# Sheet2.net
KiCad netlist of a schematic drawn in Altium Designer
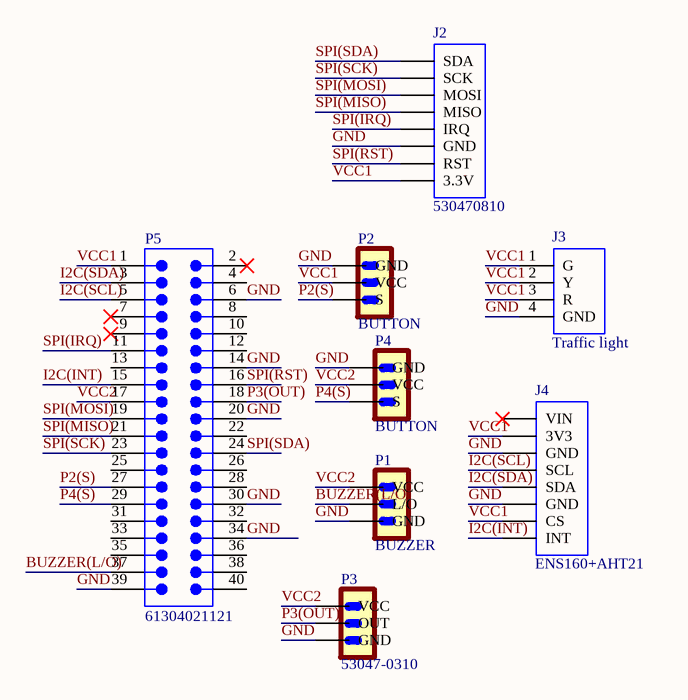
[diagram p0: Sheet2.SchDoc]

(export (version "E")
  (design (tool "Eeschema 10.0.6"))
  (components
    (comp (ref "J2") (value "530470810") (footprint "SPI") (libsource (lib "Schlib1") (part "530470810")))
    (comp (ref "J3")
      (value "Traffic light")
      (footprint "Traffic light")
      (description "2.50mm Pitch SPOXâ„¢ Wire-to-Board Header, Vertical, Shrouded, 4 Circuits, Tin (Sn) Plating")
      (fields (field (name "MF") "Molex") (field (name "MP") "22035045"))
      (libsource (lib "Schlib1") (part "Traffic light"))
    )
    (comp (ref "J4")
      (value "ENS160+AHT21")
      (footprint "ENS160+AHT21")
      (fields (field (name "MP") "530470810"))
      (libsource (lib "Schlib1") (part "ENS160+AHT21"))
    )
    (comp (ref "P1")
      (value "BUZZER")
      (footprint "BUZZER")
      (description "Connector Header Through Hole 3 position 0.049 (1.25mm)")
      (fields (field (name "MF") "Molex") (field (name "MP") "53047-0310"))
      (libsource (lib "Schlib1") (part "BUZZER"))
    )
    (comp (ref "P2")
      (value "BUTTON")
      (footprint "Button")
      (description "Connector Header Through Hole 3 position 0.049 (1.25mm)")
      (fields (field (name "MF") "Molex") (field (name "MP") "53047-0310"))
      (libsource (lib "") (part "BUTTON_1"))
    )
    (comp (ref "P3")
      (value "53047-0310")
      (footprint "SR505")
      (description "Connector Header Through Hole 3 position 0.049 (1.25mm)")
      (fields (field (name "MF") "Molex"))
      (libsource (lib "Schlib1") (part "53047-0310"))
    )
    (comp (ref "P4")
      (value "BUTTON")
      (footprint "Button2")
      (description "Connector Header Through Hole 3 position 0.049 (1.25mm)")
      (fields (field (name "MF") "Molex") (field (name "MP") "53047-0310"))
      (libsource (lib "Schlib1") (part "BUTTON"))
    )
    (comp (ref "P5")
      (value "61304021121")
      (footprint "61304021121")
      (description "WR-PHD Straight Male, PCB Header, Through Hole, 2 Rows, 40 Contacts, 2.54mm Pitch")
      (libsource (lib "Schlib1") (part "CMP-1502-01135-4"))
    )
  )
  (nets
    (net (code "1") (name "/BUZZER(L{slash}O)") (class "Default")
      (node (ref "P1") (pin "2") (pinfunction "L/O_2") (pintype "passive"))
      (node (ref "P5") (pin "37") (pinfunction "37_37") (pintype "passive"))
    )
    (net (code "2") (name "/GND") (class "Default")
      (node (ref "J2") (pin "6") (pinfunction "GND_6") (pintype "passive"))
      (node (ref "J3") (pin "4") (pinfunction "GND_4") (pintype "passive"))
      (node (ref "J4") (pin "3") (pinfunction "GND_3") (pintype "passive"))
      (node (ref "P1") (pin "1") (pinfunction "GND_1") (pintype "passive"))
      (node (ref "P2") (pin "41") (pinfunction "GND_41") (pintype "passive"))
      (node (ref "P3") (pin "1") (pinfunction "GND_1") (pintype "passive"))
      (node (ref "P4") (pin "44") (pinfunction "GND_44") (pintype "passive"))
      (node (ref "P5") (pin "14") (pinfunction "14_14") (pintype "passive"))
      (node (ref "P5") (pin "20") (pinfunction "20_20") (pintype "passive"))
      (node (ref "P5") (pin "30") (pinfunction "30_30") (pintype "passive"))
      (node (ref "P5") (pin "34") (pinfunction "34_34") (pintype "passive"))
      (node (ref "P5") (pin "39") (pinfunction "39_39") (pintype "passive"))
      (node (ref "P5") (pin "6") (pinfunction "6_6") (pintype "passive"))
    )
    (net (code "3") (name "/I2C(INT)") (class "Default")
      (node (ref "J4") (pin "8") (pinfunction "INT_8") (pintype "passive"))
      (node (ref "P5") (pin "15") (pinfunction "15_15") (pintype "passive"))
    )
    (net (code "4") (name "/I2C(SCL)") (class "Default")
      (node (ref "J4") (pin "4") (pinfunction "SCL_4") (pintype "passive"))
      (node (ref "P5") (pin "5") (pinfunction "5_5") (pintype "passive"))
    )
    (net (code "5") (name "/I2C(SDA)") (class "Default")
      (node (ref "J4") (pin "5") (pinfunction "SDA_5") (pintype "passive"))
      (node (ref "P5") (pin "3") (pinfunction "3_3") (pintype "passive"))
    )
    (net (code "6") (name "/P2(S)") (class "Default")
      (node (ref "P2") (pin "42") (pinfunction "S_42") (pintype "passive"))
      (node (ref "P5") (pin "27") (pinfunction "27_27") (pintype "passive"))
    )
    (net (code "7") (name "/P3(OUT)") (class "Default")
      (node (ref "P3") (pin "2") (pinfunction "OUT_2") (pintype "passive"))
      (node (ref "P5") (pin "18") (pinfunction "18_18") (pintype "passive"))
    )
    (net (code "8") (name "/P4(S)") (class "Default")
      (node (ref "P4") (pin "45") (pinfunction "S_45") (pintype "passive"))
      (node (ref "P5") (pin "29") (pinfunction "29_29") (pintype "passive"))
    )
    (net (code "9") (name "/SPI(IRQ)") (class "Default")
      (node (ref "J2") (pin "5") (pinfunction "IRQ_5") (pintype "passive"))
      (node (ref "P5") (pin "11") (pinfunction "11_11") (pintype "passive"))
    )
    (net (code "10") (name "/SPI(MISO)") (class "Default")
      (node (ref "J2") (pin "4") (pinfunction "MISO_4") (pintype "passive"))
      (node (ref "P5") (pin "21") (pinfunction "21_21") (pintype "passive"))
    )
    (net (code "11") (name "/SPI(MOSI)") (class "Default")
      (node (ref "J2") (pin "3") (pinfunction "MOSI_3") (pintype "passive"))
      (node (ref "P5") (pin "19") (pinfunction "19_19") (pintype "passive"))
    )
    (net (code "12") (name "/SPI(RST)") (class "Default")
      (node (ref "J2") (pin "7") (pinfunction "RST_7") (pintype "passive"))
      (node (ref "P5") (pin "16") (pinfunction "16_16") (pintype "passive"))
    )
    (net (code "13") (name "/SPI(SCK)") (class "Default")
      (node (ref "J2") (pin "2") (pinfunction "SCK_2") (pintype "passive"))
      (node (ref "P5") (pin "23") (pinfunction "23_23") (pintype "passive"))
    )
    (net (code "14") (name "/SPI(SDA)") (class "Default")
      (node (ref "J2") (pin "1") (pinfunction "SDA_1") (pintype "passive"))
      (node (ref "P5") (pin "24") (pinfunction "24_24") (pintype "passive"))
    )
    (net (code "15") (name "/VCC1") (class "Default")
      (node (ref "J2") (pin "8") (pinfunction "3.3V_8") (pintype "passive"))
      (node (ref "J3") (pin "1") (pinfunction "G_1") (pintype "passive"))
      (node (ref "J3") (pin "2") (pinfunction "Y_2") (pintype "passive"))
      (node (ref "J3") (pin "3") (pinfunction "R_3") (pintype "passive"))
      (node (ref "J4") (pin "2") (pinfunction "3V3_2") (pintype "passive"))
      (node (ref "J4") (pin "7") (pinfunction "CS_7") (pintype "passive"))
      (node (ref "P2") (pin "43") (pinfunction "VCC_43") (pintype "passive"))
      (node (ref "P5") (pin "1") (pinfunction "1_1") (pintype "passive"))
    )
    (net (code "16") (name "/VCC2") (class "Default")
      (node (ref "P1") (pin "3") (pinfunction "VCC_3") (pintype "passive"))
      (node (ref "P3") (pin "3") (pinfunction "VCC_3") (pintype "passive"))
      (node (ref "P4") (pin "46") (pinfunction "VCC_46") (pintype "passive"))
      (node (ref "P5") (pin "17") (pinfunction "17_17") (pintype "passive"))
    )
    (net (code "17") (name "unconnected-(J4-VIN-Pad1)") (class "Default")
      (node (ref "J4") (pin "1") (pinfunction "VIN_1") (pintype "passive+no_connect"))
    )
    (net (code "18") (name "unconnected-(P5-Pad2)") (class "Default")
      (node (ref "P5") (pin "2") (pinfunction "2_2") (pintype "passive+no_connect"))
    )
    (net (code "19") (name "unconnected-(P5-Pad4)") (class "Default")
      (node (ref "P5") (pin "4") (pinfunction "4_4") (pintype "passive"))
    )
    (net (code "20") (name "unconnected-(P5-Pad7)") (class "Default")
      (node (ref "P5") (pin "7") (pinfunction "7_7") (pintype "passive+no_connect"))
    )
    (net (code "21") (name "unconnected-(P5-Pad8)") (class "Default")
      (node (ref "P5") (pin "8") (pinfunction "8_8") (pintype "passive"))
    )
    (net (code "22") (name "unconnected-(P5-Pad9)") (class "Default")
      (node (ref "P5") (pin "9") (pinfunction "9_9") (pintype "passive+no_connect"))
    )
    (net (code "23") (name "unconnected-(P5-Pad10)") (class "Default")
      (node (ref "P5") (pin "10") (pinfunction "10_10") (pintype "passive"))
    )
    (net (code "24") (name "unconnected-(P5-Pad12)") (class "Default")
      (node (ref "P5") (pin "12") (pinfunction "12_12") (pintype "passive"))
    )
    (net (code "25") (name "unconnected-(P5-Pad13)") (class "Default")
      (node (ref "P5") (pin "13") (pinfunction "13_13") (pintype "passive"))
    )
    (net (code "26") (name "unconnected-(P5-Pad22)") (class "Default")
      (node (ref "P5") (pin "22") (pinfunction "22_22") (pintype "passive"))
    )
    (net (code "27") (name "unconnected-(P5-Pad25)") (class "Default")
      (node (ref "P5") (pin "25") (pinfunction "25_25") (pintype "passive"))
    )
    (net (code "28") (name "unconnected-(P5-Pad26)") (class "Default")
      (node (ref "P5") (pin "26") (pinfunction "26_26") (pintype "passive"))
    )
    (net (code "29") (name "unconnected-(P5-Pad28)") (class "Default")
      (node (ref "P5") (pin "28") (pinfunction "28_28") (pintype "passive"))
    )
    (net (code "30") (name "unconnected-(P5-Pad31)") (class "Default")
      (node (ref "P5") (pin "31") (pinfunction "31_31") (pintype "passive"))
    )
    (net (code "31") (name "unconnected-(P5-Pad32)") (class "Default")
      (node (ref "P5") (pin "32") (pinfunction "32_32") (pintype "passive"))
    )
    (net (code "32") (name "unconnected-(P5-Pad33)") (class "Default")
      (node (ref "P5") (pin "33") (pinfunction "33_33") (pintype "passive"))
    )
    (net (code "33") (name "unconnected-(P5-Pad35)") (class "Default")
      (node (ref "P5") (pin "35") (pinfunction "35_35") (pintype "passive"))
    )
    (net (code "34") (name "unconnected-(P5-Pad36)") (class "Default")
      (node (ref "P5") (pin "36") (pinfunction "36_36") (pintype "passive"))
    )
    (net (code "35") (name "unconnected-(P5-Pad38)") (class "Default")
      (node (ref "P5") (pin "38") (pinfunction "38_38") (pintype "passive"))
    )
    (net (code "36") (name "unconnected-(P5-Pad40)") (class "Default")
      (node (ref "P5") (pin "40") (pinfunction "40_40") (pintype "passive"))
    )
  )
)
